# vdmotCtrl_v1.net
KiCad netlist of a schematic drawn in EAGLE
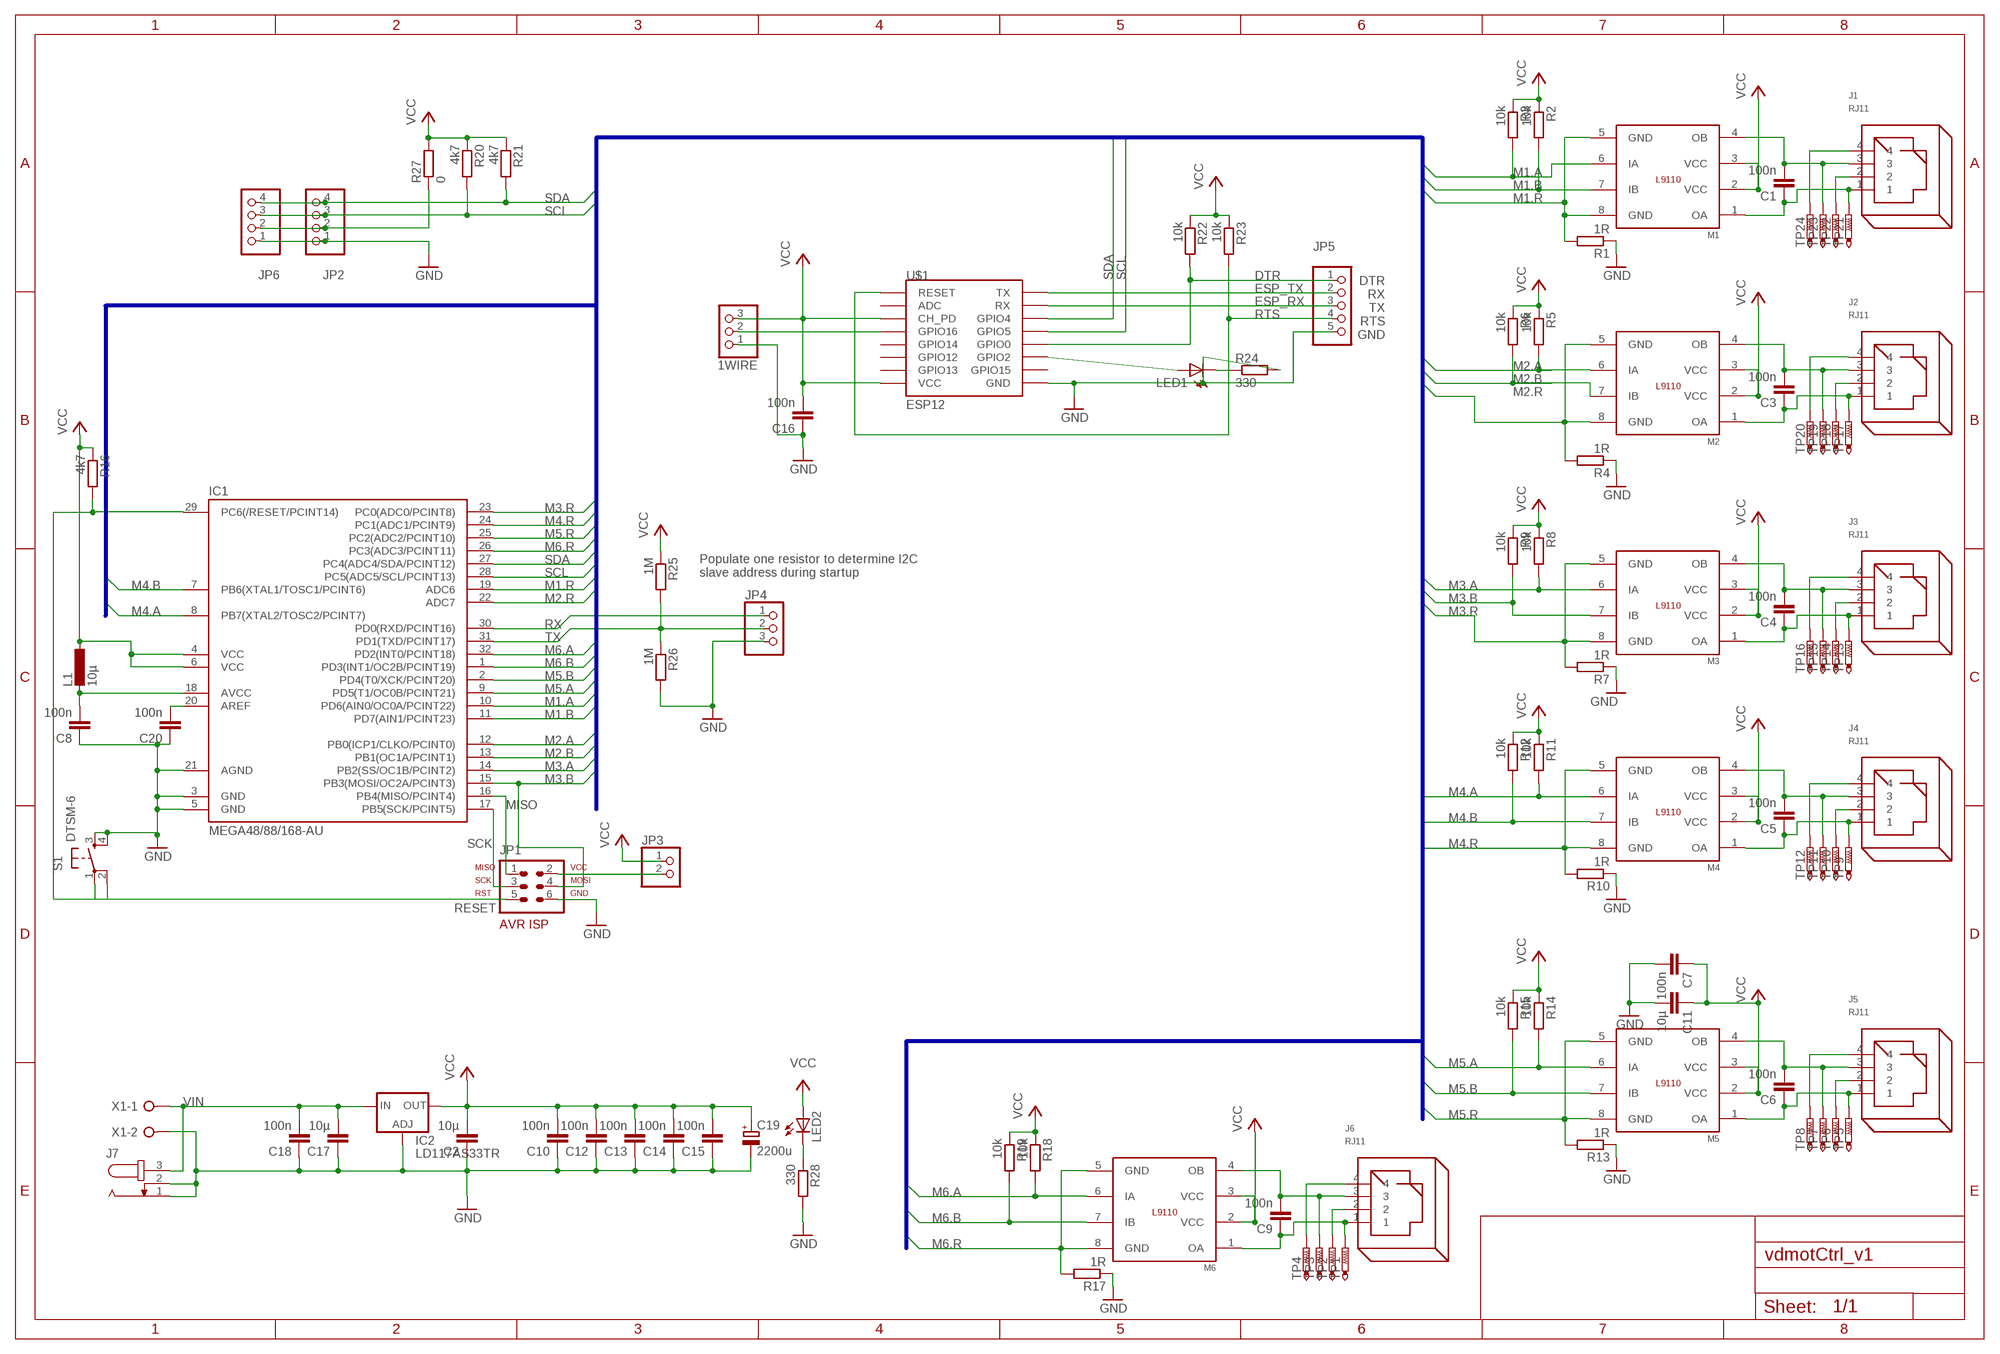
[diagram p0: schematic, sheet 1]

(export (version "E")
  (design (tool "Eeschema 10.0.6"))
  (components
    (comp (ref "1WIRE")
      (value "PINHD-1X3")
      (footprint "eagle-import:1X03")
      (libsource (lib "eagle-import") (part "PINHD-1X3"))
    )
    (comp (ref "C1")
      (value "100n")
      (footprint "eagle-import:C0805")
      (libsource (lib "eagle-import") (part "C-EUC0805"))
    )
    (comp (ref "C2")
      (value "10µ")
      (footprint "eagle-import:C0805")
      (libsource (lib "eagle-import") (part "C-EUC0805"))
    )
    (comp (ref "C3")
      (value "100n")
      (footprint "eagle-import:C0805")
      (libsource (lib "eagle-import") (part "C-EUC0805"))
    )
    (comp (ref "C4")
      (value "100n")
      (footprint "eagle-import:C0805")
      (libsource (lib "eagle-import") (part "C-EUC0805"))
    )
    (comp (ref "C5")
      (value "100n")
      (footprint "eagle-import:C0805")
      (libsource (lib "eagle-import") (part "C-EUC0805"))
    )
    (comp (ref "C6")
      (value "100n")
      (footprint "eagle-import:C0805")
      (libsource (lib "eagle-import") (part "C-EUC0805"))
    )
    (comp (ref "C7")
      (value "100n")
      (footprint "eagle-import:C0805")
      (libsource (lib "eagle-import") (part "C-EUC0805"))
    )
    (comp (ref "C8")
      (value "100n")
      (footprint "eagle-import:C0805")
      (libsource (lib "eagle-import") (part "C-EUC0805"))
    )
    (comp (ref "C9")
      (value "100n")
      (footprint "eagle-import:C0805")
      (libsource (lib "eagle-import") (part "C-EUC0805"))
    )
    (comp (ref "C10")
      (value "100n")
      (footprint "eagle-import:C0805")
      (libsource (lib "eagle-import") (part "C-EUC0805"))
    )
    (comp (ref "C11")
      (value "10µ")
      (footprint "eagle-import:C0805")
      (libsource (lib "eagle-import") (part "C-EUC0805"))
    )
    (comp (ref "C12")
      (value "100n")
      (footprint "eagle-import:C0805")
      (libsource (lib "eagle-import") (part "C-EUC0805"))
    )
    (comp (ref "C13")
      (value "100n")
      (footprint "eagle-import:C0805")
      (libsource (lib "eagle-import") (part "C-EUC0805"))
    )
    (comp (ref "C14")
      (value "100n")
      (footprint "eagle-import:C0805")
      (libsource (lib "eagle-import") (part "C-EUC0805"))
    )
    (comp (ref "C15")
      (value "100n")
      (footprint "eagle-import:C0805")
      (libsource (lib "eagle-import") (part "C-EUC0805"))
    )
    (comp (ref "C16")
      (value "100n")
      (footprint "eagle-import:C0805")
      (libsource (lib "eagle-import") (part "C-EUC0805"))
    )
    (comp (ref "C17")
      (value "10µ")
      (footprint "eagle-import:C0805")
      (libsource (lib "eagle-import") (part "C-EUC0805"))
    )
    (comp (ref "C18")
      (value "100n")
      (footprint "eagle-import:C0805")
      (libsource (lib "eagle-import") (part "C-EUC0805"))
    )
    (comp (ref "C19")
      (value "2200u")
      (footprint "eagle-import:E5-10,5")
      (libsource (lib "eagle-import") (part "CPOL-EUE5-10.5"))
    )
    (comp (ref "C20")
      (value "100n")
      (footprint "eagle-import:C0805")
      (libsource (lib "eagle-import") (part "C-EUC0805"))
    )
    (comp (ref "IC1")
      (value "MEGA48/88/168-AU")
      (footprint "eagle-import:TQFP32-08")
      (libsource (lib "eagle-import") (part "MEGA48/88/168-AU"))
    )
    (comp (ref "IC2")
      (value "LD117AS33TR")
      (footprint "eagle-import:SOT223")
      (libsource (lib "eagle-import") (part "LD117A?S33TR"))
    )
    (comp (ref "J1")
      (value "RJ11")
      (footprint "eagle-import:RJ11")
      (libsource (lib "eagle-import") (part "RJ11"))
    )
    (comp (ref "J2")
      (value "RJ11")
      (footprint "eagle-import:RJ11")
      (libsource (lib "eagle-import") (part "RJ11"))
    )
    (comp (ref "J3")
      (value "RJ11")
      (footprint "eagle-import:RJ11")
      (libsource (lib "eagle-import") (part "RJ11"))
    )
    (comp (ref "J4")
      (value "RJ11")
      (footprint "eagle-import:RJ11")
      (libsource (lib "eagle-import") (part "RJ11"))
    )
    (comp (ref "J5")
      (value "RJ11")
      (footprint "eagle-import:RJ11")
      (libsource (lib "eagle-import") (part "RJ11"))
    )
    (comp (ref "J6")
      (value "RJ11")
      (footprint "eagle-import:RJ11")
      (libsource (lib "eagle-import") (part "RJ11"))
    )
    (comp (ref "J7")
      (value "JACK-PLUG0")
      (footprint "eagle-import:SPC4077")
      (libsource (lib "eagle-import") (part "JACK-PLUG0"))
    )
    (comp (ref "JP1")
      (value "AVR-ISP-6VERT")
      (footprint "eagle-import:AVR-ISP-6")
      (libsource (lib "eagle-import") (part "AVR-ISP-6VERT"))
    )
    (comp (ref "JP2")
      (value "PINHD-1X4")
      (footprint "eagle-import:1X04")
      (libsource (lib "eagle-import") (part "PINHD-1X4"))
    )
    (comp (ref "JP3")
      (value "PINHD-1X2")
      (footprint "eagle-import:1X02")
      (libsource (lib "eagle-import") (part "PINHD-1X2"))
    )
    (comp (ref "JP4")
      (value "PINHD-1X3")
      (footprint "eagle-import:1X03")
      (libsource (lib "eagle-import") (part "PINHD-1X3"))
    )
    (comp (ref "JP5")
      (value "PINHD-1X5")
      (footprint "eagle-import:1X05")
      (libsource (lib "eagle-import") (part "PINHD-1X5"))
    )
    (comp (ref "JP6")
      (value "PINHD-1X4")
      (footprint "eagle-import:1X04")
      (libsource (lib "eagle-import") (part "PINHD-1X4"))
    )
    (comp (ref "L1")
      (value "10µ")
      (footprint "eagle-import:0204_7")
      (libsource (lib "eagle-import") (part "L-EU0204/7"))
    )
    (comp (ref "LED1")
      (value "RED")
      (footprint "eagle-import:SML0805")
      (libsource (lib "eagle-import") (part "LEDSML0805"))
    )
    (comp (ref "LED2")
      (value "RED")
      (footprint "eagle-import:SML0805")
      (libsource (lib "eagle-import") (part "LEDSML0805"))
    )
    (comp (ref "M1")
      (value "L9110")
      (footprint "eagle-import:SO8P")
      (libsource (lib "eagle-import") (part "L9110"))
    )
    (comp (ref "M2")
      (value "L9110")
      (footprint "eagle-import:SO8P")
      (libsource (lib "eagle-import") (part "L9110"))
    )
    (comp (ref "M3")
      (value "L9110")
      (footprint "eagle-import:SO8P")
      (libsource (lib "eagle-import") (part "L9110"))
    )
    (comp (ref "M4")
      (value "L9110")
      (footprint "eagle-import:SO8P")
      (libsource (lib "eagle-import") (part "L9110"))
    )
    (comp (ref "M5")
      (value "L9110")
      (footprint "eagle-import:SO8P")
      (libsource (lib "eagle-import") (part "L9110"))
    )
    (comp (ref "M6")
      (value "L9110")
      (footprint "eagle-import:SO8P")
      (libsource (lib "eagle-import") (part "L9110"))
    )
    (comp (ref "R1")
      (value "1R")
      (footprint "eagle-import:R0805")
      (libsource (lib "eagle-import") (part "R-EU_R0805"))
    )
    (comp (ref "R2")
      (value "10k")
      (footprint "eagle-import:R0805")
      (libsource (lib "eagle-import") (part "R-EU_R0805"))
    )
    (comp (ref "R3")
      (value "10k")
      (footprint "eagle-import:R0805")
      (libsource (lib "eagle-import") (part "R-EU_R0805"))
    )
    (comp (ref "R4")
      (value "1R")
      (footprint "eagle-import:R0805")
      (libsource (lib "eagle-import") (part "R-EU_R0805"))
    )
    (comp (ref "R5")
      (value "10k")
      (footprint "eagle-import:R0805")
      (libsource (lib "eagle-import") (part "R-EU_R0805"))
    )
    (comp (ref "R6")
      (value "10k")
      (footprint "eagle-import:R0805")
      (libsource (lib "eagle-import") (part "R-EU_R0805"))
    )
    (comp (ref "R7")
      (value "1R")
      (footprint "eagle-import:R0805")
      (libsource (lib "eagle-import") (part "R-EU_R0805"))
    )
    (comp (ref "R8")
      (value "10k")
      (footprint "eagle-import:R0805")
      (libsource (lib "eagle-import") (part "R-EU_R0805"))
    )
    (comp (ref "R9")
      (value "10k")
      (footprint "eagle-import:R0805")
      (libsource (lib "eagle-import") (part "R-EU_R0805"))
    )
    (comp (ref "R10")
      (value "1R")
      (footprint "eagle-import:R0805")
      (libsource (lib "eagle-import") (part "R-EU_R0805"))
    )
    (comp (ref "R11")
      (value "10k")
      (footprint "eagle-import:R0805")
      (libsource (lib "eagle-import") (part "R-EU_R0805"))
    )
    (comp (ref "R12")
      (value "10k")
      (footprint "eagle-import:R0805")
      (libsource (lib "eagle-import") (part "R-EU_R0805"))
    )
    (comp (ref "R13")
      (value "1R")
      (footprint "eagle-import:R0805")
      (libsource (lib "eagle-import") (part "R-EU_R0805"))
    )
    (comp (ref "R14")
      (value "10k")
      (footprint "eagle-import:R0805")
      (libsource (lib "eagle-import") (part "R-EU_R0805"))
    )
    (comp (ref "R15")
      (value "10k")
      (footprint "eagle-import:R0805")
      (libsource (lib "eagle-import") (part "R-EU_R0805"))
    )
    (comp (ref "R16")
      (value "4k7")
      (footprint "eagle-import:R0805")
      (libsource (lib "eagle-import") (part "R-EU_R0805"))
    )
    (comp (ref "R17")
      (value "1R")
      (footprint "eagle-import:R0805")
      (libsource (lib "eagle-import") (part "R-EU_R0805"))
    )
    (comp (ref "R18")
      (value "10k")
      (footprint "eagle-import:R0805")
      (libsource (lib "eagle-import") (part "R-EU_R0805"))
    )
    (comp (ref "R19")
      (value "10k")
      (footprint "eagle-import:R0805")
      (libsource (lib "eagle-import") (part "R-EU_R0805"))
    )
    (comp (ref "R20")
      (value "4k7")
      (footprint "eagle-import:R0805")
      (libsource (lib "eagle-import") (part "R-EU_R0805"))
    )
    (comp (ref "R21")
      (value "4k7")
      (footprint "eagle-import:R0805")
      (libsource (lib "eagle-import") (part "R-EU_R0805"))
    )
    (comp (ref "R22")
      (value "10k")
      (footprint "eagle-import:R0805")
      (libsource (lib "eagle-import") (part "R-EU_R0805"))
    )
    (comp (ref "R23")
      (value "10k")
      (footprint "eagle-import:R0805")
      (libsource (lib "eagle-import") (part "R-EU_R0805"))
    )
    (comp (ref "R24")
      (value "330")
      (footprint "eagle-import:R0805")
      (libsource (lib "eagle-import") (part "R-EU_R0805"))
    )
    (comp (ref "R25")
      (value "1M")
      (footprint "eagle-import:R0805")
      (libsource (lib "eagle-import") (part "R-EU_R0805"))
    )
    (comp (ref "R26")
      (value "1M")
      (footprint "eagle-import:R0805")
      (libsource (lib "eagle-import") (part "R-EU_R0805"))
    )
    (comp (ref "R27")
      (value "0")
      (footprint "eagle-import:M0805")
      (libsource (lib "eagle-import") (part "R-EU_M0805"))
    )
    (comp (ref "R28")
      (value "330")
      (footprint "eagle-import:R0805")
      (libsource (lib "eagle-import") (part "R-EU_R0805"))
    )
    (comp (ref "S1")
      (value "DTSM-6")
      (footprint "eagle-import:DTSM-6")
      (libsource (lib "eagle-import") (part "DTSM-6"))
    )
    (comp (ref "TP1")
      (value "PTR1TP15SQ")
      (footprint "eagle-import:TP15SQ")
      (libsource (lib "eagle-import") (part "PTR1TP15SQ"))
    )
    (comp (ref "TP2")
      (value "PTR1TP15SQ")
      (footprint "eagle-import:TP15SQ")
      (libsource (lib "eagle-import") (part "PTR1TP15SQ"))
    )
    (comp (ref "TP3")
      (value "PTR1TP15SQ")
      (footprint "eagle-import:TP15SQ")
      (libsource (lib "eagle-import") (part "PTR1TP15SQ"))
    )
    (comp (ref "TP4")
      (value "PTR1TP15SQ")
      (footprint "eagle-import:TP15SQ")
      (libsource (lib "eagle-import") (part "PTR1TP15SQ"))
    )
    (comp (ref "TP5")
      (value "PTR1TP15SQ")
      (footprint "eagle-import:TP15SQ")
      (libsource (lib "eagle-import") (part "PTR1TP15SQ"))
    )
    (comp (ref "TP6")
      (value "PTR1TP15SQ")
      (footprint "eagle-import:TP15SQ")
      (libsource (lib "eagle-import") (part "PTR1TP15SQ"))
    )
    (comp (ref "TP7")
      (value "PTR1TP15SQ")
      (footprint "eagle-import:TP15SQ")
      (libsource (lib "eagle-import") (part "PTR1TP15SQ"))
    )
    (comp (ref "TP8")
      (value "PTR1TP15SQ")
      (footprint "eagle-import:TP15SQ")
      (libsource (lib "eagle-import") (part "PTR1TP15SQ"))
    )
    (comp (ref "TP9")
      (value "PTR1TP15SQ")
      (footprint "eagle-import:TP15SQ")
      (libsource (lib "eagle-import") (part "PTR1TP15SQ"))
    )
    (comp (ref "TP10")
      (value "PTR1TP15SQ")
      (footprint "eagle-import:TP15SQ")
      (libsource (lib "eagle-import") (part "PTR1TP15SQ"))
    )
    (comp (ref "TP11")
      (value "PTR1TP15SQ")
      (footprint "eagle-import:TP15SQ")
      (libsource (lib "eagle-import") (part "PTR1TP15SQ"))
    )
    (comp (ref "TP12")
      (value "PTR1TP15SQ")
      (footprint "eagle-import:TP15SQ")
      (libsource (lib "eagle-import") (part "PTR1TP15SQ"))
    )
    (comp (ref "TP13")
      (value "PTR1TP15SQ")
      (footprint "eagle-import:TP15SQ")
      (libsource (lib "eagle-import") (part "PTR1TP15SQ"))
    )
    (comp (ref "TP14")
      (value "PTR1TP15SQ")
      (footprint "eagle-import:TP15SQ")
      (libsource (lib "eagle-import") (part "PTR1TP15SQ"))
    )
    (comp (ref "TP15")
      (value "PTR1TP15SQ")
      (footprint "eagle-import:TP15SQ")
      (libsource (lib "eagle-import") (part "PTR1TP15SQ"))
    )
    (comp (ref "TP16")
      (value "PTR1TP15SQ")
      (footprint "eagle-import:TP15SQ")
      (libsource (lib "eagle-import") (part "PTR1TP15SQ"))
    )
    (comp (ref "TP17")
      (value "PTR1TP15SQ")
      (footprint "eagle-import:TP15SQ")
      (libsource (lib "eagle-import") (part "PTR1TP15SQ"))
    )
    (comp (ref "TP18")
      (value "PTR1TP15SQ")
      (footprint "eagle-import:TP15SQ")
      (libsource (lib "eagle-import") (part "PTR1TP15SQ"))
    )
    (comp (ref "TP19")
      (value "PTR1TP15SQ")
      (footprint "eagle-import:TP15SQ")
      (libsource (lib "eagle-import") (part "PTR1TP15SQ"))
    )
    (comp (ref "TP20")
      (value "PTR1TP15SQ")
      (footprint "eagle-import:TP15SQ")
      (libsource (lib "eagle-import") (part "PTR1TP15SQ"))
    )
    (comp (ref "TP21")
      (value "PTR1TP15SQ")
      (footprint "eagle-import:TP15SQ")
      (libsource (lib "eagle-import") (part "PTR1TP15SQ"))
    )
    (comp (ref "TP22")
      (value "PTR1TP15SQ")
      (footprint "eagle-import:TP15SQ")
      (libsource (lib "eagle-import") (part "PTR1TP15SQ"))
    )
    (comp (ref "TP23")
      (value "PTR1TP15SQ")
      (footprint "eagle-import:TP15SQ")
      (libsource (lib "eagle-import") (part "PTR1TP15SQ"))
    )
    (comp (ref "TP24")
      (value "PTR1TP15SQ")
      (footprint "eagle-import:TP15SQ")
      (libsource (lib "eagle-import") (part "PTR1TP15SQ"))
    )
    (comp (ref "U$1")
      (value "ESP12")
      (footprint "eagle-import:ESP12")
      (libsource (lib "eagle-import") (part "ESP12"))
    )
    (comp (ref "X1")
      (value "W237-02P")
      (footprint "eagle-import:W237-132")
      (libsource (lib "eagle-import") (part "W237-02P"))
    )
  )
  (nets
    (net (code "1") (name "/DTR") (class "Default")
      (node (ref "JP5") (pin "1") (pinfunction "1_1") (pintype "passive"))
      (node (ref "R22") (pin "2") (pinfunction "2_2") (pintype "passive"))
      (node (ref "U$1") (pin "GPIO0") (pinfunction "GPIO0_GPIO0") (pintype "bidirectional"))
    )
    (net (code "2") (name "/ESP_RX") (class "Default")
      (node (ref "JP5") (pin "3") (pinfunction "3_3") (pintype "passive"))
      (node (ref "U$1") (pin "RX") (pinfunction "RX_RX") (pintype "bidirectional"))
    )
    (net (code "3") (name "/ESP_TX") (class "Default")
      (node (ref "JP5") (pin "2") (pinfunction "2_2") (pintype "passive"))
      (node (ref "U$1") (pin "TX") (pinfunction "TX_TX") (pintype "bidirectional"))
    )
    (net (code "4") (name "/M1.A") (class "Default")
      (node (ref "IC1") (pin "10") (pinfunction "PD6(AIN0/OC0A/PCINT22)_10") (pintype "bidirectional"))
      (node (ref "M1") (pin "6") (pinfunction "IA_6") (pintype "bidirectional"))
      (node (ref "R3") (pin "2") (pinfunction "2_2") (pintype "passive"))
    )
    (net (code "5") (name "/M1.B") (class "Default")
      (node (ref "IC1") (pin "11") (pinfunction "PD7(AIN1/PCINT23)_11") (pintype "bidirectional"))
      (node (ref "M1") (pin "7") (pinfunction "IB_7") (pintype "bidirectional"))
      (node (ref "R2") (pin "2") (pinfunction "2_2") (pintype "passive"))
    )
    (net (code "6") (name "/M1.R") (class "Default")
      (node (ref "IC1") (pin "19") (pinfunction "ADC6_19") (pintype "passive"))
      (node (ref "M1") (pin "5") (pinfunction "GND_5") (pintype "bidirectional"))
      (node (ref "M1") (pin "8") (pinfunction "GND_8") (pintype "bidirectional"))
      (node (ref "R1") (pin "2") (pinfunction "2_2") (pintype "passive"))
    )
    (net (code "7") (name "/M2.A") (class "Default")
      (node (ref "IC1") (pin "12") (pinfunction "PB0(ICP1/CLKO/PCINT0)_12") (pintype "bidirectional"))
      (node (ref "M2") (pin "6") (pinfunction "IA_6") (pintype "bidirectional"))
      (node (ref "R5") (pin "2") (pinfunction "2_2") (pintype "passive"))
    )
    (net (code "8") (name "/M2.B") (class "Default")
      (node (ref "IC1") (pin "13") (pinfunction "PB1(OC1A/PCINT1)_13") (pintype "bidirectional"))
      (node (ref "M2") (pin "7") (pinfunction "IB_7") (pintype "bidirectional"))
      (node (ref "R6") (pin "2") (pinfunction "2_2") (pintype "passive"))
    )
    (net (code "9") (name "/M2.R") (class "Default")
      (node (ref "IC1") (pin "22") (pinfunction "ADC7_22") (pintype "passive"))
      (node (ref "M2") (pin "5") (pinfunction "GND_5") (pintype "bidirectional"))
      (node (ref "M2") (pin "8") (pinfunction "GND_8") (pintype "bidirectional"))
      (node (ref "R4") (pin "2") (pinfunction "2_2") (pintype "passive"))
    )
    (net (code "10") (name "/M3.A") (class "Default")
      (node (ref "IC1") (pin "14") (pinfunction "PB2(SS/OC1B/PCINT2)_14") (pintype "bidirectional"))
      (node (ref "M3") (pin "6") (pinfunction "IA_6") (pintype "bidirectional"))
      (node (ref "R8") (pin "2") (pinfunction "2_2") (pintype "passive"))
    )
    (net (code "11") (name "/M3.B") (class "Default")
      (node (ref "IC1") (pin "15") (pinfunction "PB3(MOSI/OC2A/PCINT3)_15") (pintype "bidirectional"))
      (node (ref "JP1") (pin "4") (pinfunction "4_4") (pintype "passive"))
      (node (ref "M3") (pin "7") (pinfunction "IB_7") (pintype "bidirectional"))
      (node (ref "R9") (pin "2") (pinfunction "2_2") (pintype "passive"))
    )
    (net (code "12") (name "/M3.R") (class "Default")
      (node (ref "IC1") (pin "23") (pinfunction "PC0(ADC0/PCINT8)_23") (pintype "bidirectional"))
      (node (ref "M3") (pin "5") (pinfunction "GND_5") (pintype "bidirectional"))
      (node (ref "M3") (pin "8") (pinfunction "GND_8") (pintype "bidirectional"))
      (node (ref "R7") (pin "2") (pinfunction "2_2") (pintype "passive"))
    )
    (net (code "13") (name "/M4.A") (class "Default")
      (node (ref "IC1") (pin "8") (pinfunction "PB7(XTAL2/TOSC2/PCINT7)_8") (pintype "bidirectional"))
      (node (ref "M4") (pin "6") (pinfunction "IA_6") (pintype "bidirectional"))
      (node (ref "R11") (pin "2") (pinfunction "2_2") (pintype "passive"))
    )
    (net (code "14") (name "/M4.B") (class "Default")
      (node (ref "IC1") (pin "7") (pinfunction "PB6(XTAL1/TOSC1/PCINT6)_7") (pintype "bidirectional"))
      (node (ref "M4") (pin "7") (pinfunction "IB_7") (pintype "bidirectional"))
      (node (ref "R12") (pin "2") (pinfunction "2_2") (pintype "passive"))
    )
    (net (code "15") (name "/M4.R") (class "Default")
      (node (ref "IC1") (pin "24") (pinfunction "PC1(ADC1/PCINT9)_24") (pintype "bidirectional"))
      (node (ref "M4") (pin "5") (pinfunction "GND_5") (pintype "bidirectional"))
      (node (ref "M4") (pin "8") (pinfunction "GND_8") (pintype "bidirectional"))
      (node (ref "R10") (pin "2") (pinfunction "2_2") (pintype "passive"))
    )
    (net (code "16") (name "/M5.A") (class "Default")
      (node (ref "IC1") (pin "9") (pinfunction "PD5(T1/OC0B/PCINT21)_9") (pintype "bidirectional"))
      (node (ref "M5") (pin "6") (pinfunction "IA_6") (pintype "bidirectional"))
      (node (ref "R14") (pin "2") (pinfunction "2_2") (pintype "passive"))
    )
    (net (code "17") (name "/M5.B") (class "Default")
      (node (ref "IC1") (pin "2") (pinfunction "PD4(T0/XCK/PCINT20)_2") (pintype "bidirectional"))
      (node (ref "M5") (pin "7") (pinfunction "IB_7") (pintype "bidirectional"))
      (node (ref "R15") (pin "2") (pinfunction "2_2") (pintype "passive"))
    )
    (net (code "18") (name "/M5.R") (class "Default")
      (node (ref "IC1") (pin "25") (pinfunction "PC2(ADC2/PCINT10)_25") (pintype "bidirectional"))
      (node (ref "M5") (pin "5") (pinfunction "GND_5") (pintype "bidirectional"))
      (node (ref "M5") (pin "8") (pinfunction "GND_8") (pintype "bidirectional"))
      (node (ref "R13") (pin "2") (pinfunction "2_2") (pintype "passive"))
    )
    (net (code "19") (name "/M6.A") (class "Default")
      (node (ref "IC1") (pin "32") (pinfunction "PD2(INT0/PCINT18)_32") (pintype "bidirectional"))
      (node (ref "M6") (pin "6") (pinfunction "IA_6") (pintype "bidirectional"))
      (node (ref "R18") (pin "2") (pinfunction "2_2") (pintype "passive"))
    )
    (net (code "20") (name "/M6.B") (class "Default")
      (node (ref "IC1") (pin "1") (pinfunction "PD3(INT1/OC2B/PCINT19)_1") (pintype "bidirectional"))
      (node (ref "M6") (pin "7") (pinfunction "IB_7") (pintype "bidirectional"))
      (node (ref "R19") (pin "2") (pinfunction "2_2") (pintype "passive"))
    )
    (net (code "21") (name "/M6.R") (class "Default")
      (node (ref "IC1") (pin "26") (pinfunction "PC3(ADC3/PCINT11)_26") (pintype "bidirectional"))
      (node (ref "M6") (pin "5") (pinfunction "GND_5") (pintype "bidirectional"))
      (node (ref "M6") (pin "8") (pinfunction "GND_8") (pintype "bidirectional"))
      (node (ref "R17") (pin "2") (pinfunction "2_2") (pintype "passive"))
    )
    (net (code "22") (name "/MISO") (class "Default")
      (node (ref "IC1") (pin "16") (pinfunction "PB4(MISO/PCINT4)_16") (pintype "bidirectional"))
      (node (ref "JP1") (pin "1") (pinfunction "1_1") (pintype "passive"))
    )
    (net (code "23") (name "/RESET") (class "Default")
      (node (ref "IC1") (pin "29") (pinfunction "PC6(/RESET/PCINT14)_29") (pintype "bidirectional"))
      (node (ref "JP1") (pin "5") (pinfunction "5_5") (pintype "passive"))
      (node (ref "R16") (pin "2") (pinfunction "2_2") (pintype "passive"))
      (node (ref "S1") (pin "1") (pinfunction "1_1") (pintype "passive"))
      (node (ref "S1") (pin "2") (pinfunction "2_2") (pintype "passive"))
    )
    (net (code "24") (name "/RTS") (class "Default")
      (node (ref "JP5") (pin "4") (pinfunction "4_4") (pintype "passive"))
      (node (ref "R23") (pin "2") (pinfunction "2_2") (pintype "passive"))
      (node (ref "U$1") (pin "RESET") (pinfunction "RESET_RESET") (pintype "bidirectional"))
    )
    (net (code "25") (name "/RX") (class "Default")
      (node (ref "IC1") (pin "30") (pinfunction "PD0(RXD/PCINT16)_30") (pintype "bidirectional"))
      (node (ref "JP4") (pin "1") (pinfunction "1_1") (pintype "passive"))
    )
    (net (code "26") (name "/SCK") (class "Default")
      (node (ref "IC1") (pin "17") (pinfunction "PB5(SCK/PCINT5)_17") (pintype "bidirectional"))
      (node (ref "JP1") (pin "3") (pinfunction "3_3") (pintype "passive"))
    )
    (net (code "27") (name "/SCL") (class "Default")
      (node (ref "IC1") (pin "28") (pinfunction "PC5(ADC5/SCL/PCINT13)_28") (pintype "bidirectional"))
      (node (ref "JP2") (pin "3") (pinfunction "3_3") (pintype "passive"))
      (node (ref "JP6") (pin "3") (pinfunction "3_3") (pintype "passive"))
      (node (ref "R20") (pin "2") (pinfunction "2_2") (pintype "passive"))
      (node (ref "U$1") (pin "GPIO5") (pinfunction "GPIO5_GPIO5") (pintype "bidirectional"))
    )
    (net (code "28") (name "/SDA") (class "Default")
      (node (ref "IC1") (pin "27") (pinfunction "PC4(ADC4/SDA/PCINT12)_27") (pintype "bidirectional"))
      (node (ref "JP2") (pin "4") (pinfunction "4_4") (pintype "passive"))
      (node (ref "JP6") (pin "4") (pinfunction "4_4") (pintype "passive"))
      (node (ref "R21") (pin "2") (pinfunction "2_2") (pintype "passive"))
      (node (ref "U$1") (pin "GPIO4") (pinfunction "GPIO4_GPIO4") (pintype "bidirectional"))
    )
    (net (code "29") (name "/TX") (class "Default")
      (node (ref "IC1") (pin "31") (pinfunction "PD1(TXD/PCINT17)_31") (pintype "bidirectional"))
      (node (ref "JP4") (pin "2") (pinfunction "2_2") (pintype "passive"))
      (node (ref "R25") (pin "2") (pinfunction "2_2") (pintype "passive"))
      (node (ref "R26") (pin "1") (pinfunction "1_1") (pintype "passive"))
    )
    (net (code "30") (name "/VIN") (class "Default")
      (node (ref "C17") (pin "2") (pinfunction "2_2") (pintype "passive"))
      (node (ref "C18") (pin "2") (pinfunction "2_2") (pintype "passive"))
      (node (ref "IC2") (pin "3") (pinfunction "IN_3") (pintype "input"))
      (node (ref "J7") (pin "3") (pinfunction "3_3") (pintype "passive"))
      (node (ref "X1") (pin "1") (pinfunction "KL_1") (pintype "passive"))
    )
    (net (code "31") (name "GND") (class "Default")
      (node (ref "1WIRE") (pin "1") (pinfunction "1_1") (pintype "passive"))
      (node (ref "C10") (pin "1") (pinfunction "1_1") (pintype "passive"))
      (node (ref "C11") (pin "2") (pinfunction "2_2") (pintype "passive"))
      (node (ref "C12") (pin "1") (pinfunction "1_1") (pintype "passive"))
      (node (ref "C13") (pin "1") (pinfunction "1_1") (pintype "passive"))
      (node (ref "C14") (pin "1") (pinfunction "1_1") (pintype "passive"))
      (node (ref "C15") (pin "1") (pinfunction "1_1") (pintype "passive"))
      (node (ref "C16") (pin "1") (pinfunction "1_1") (pintype "passive"))
      (node (ref "C17") (pin "1") (pinfunction "1_1") (pintype "passive"))
      (node (ref "C18") (pin "1") (pinfunction "1_1") (pintype "passive"))
      (node (ref "C19") (pin "-") (pinfunction "-_-") (pintype "passive"))
      (node (ref "C2") (pin "1") (pinfunction "1_1") (pintype "passive"))
      (node (ref "C20") (pin "1") (pinfunction "1_1") (pintype "passive"))
      (node (ref "C7") (pin "2") (pinfunction "2_2") (pintype "passive"))
      (node (ref "C8") (pin "1") (pinfunction "1_1") (pintype "passive"))
      (node (ref "IC1") (pin "21") (pinfunction "AGND_21") (pintype "power_in"))
      (node (ref "IC1") (pin "3") (pinfunction "GND_3") (pintype "power_in"))
      (node (ref "IC1") (pin "5") (pinfunction "GND_5") (pintype "power_in"))
      (node (ref "IC2") (pin "1") (pinfunction "ADJ_1") (pintype "input"))
      (node (ref "J7") (pin "1") (pinfunction "1_1") (pintype "passive"))
      (node (ref "J7") (pin "2") (pinfunction "2_2") (pintype "passive"))
      (node (ref "JP1") (pin "6") (pinfunction "6_6") (pintype "passive"))
      (node (ref "JP2") (pin "1") (pinfunction "1_1") (pintype "passive"))
      (node (ref "JP4") (pin "3") (pinfunction "3_3") (pintype "passive"))
      (node (ref "JP5") (pin "5") (pinfunction "5_5") (pintype "passive"))
      (node (ref "JP6") (pin "1") (pinfunction "1_1") (pintype "passive"))
      (node (ref "R1") (pin "1") (pinfunction "1_1") (pintype "passive"))
      (node (ref "R10") (pin "1") (pinfunction "1_1") (pintype "passive"))
      (node (ref "R13") (pin "1") (pinfunction "1_1") (pintype "passive"))
      (node (ref "R17") (pin "1") (pinfunction "1_1") (pintype "passive"))
      (node (ref "R24") (pin "2") (pinfunction "2_2") (pintype "passive"))
      (node (ref "R26") (pin "2") (pinfunction "2_2") (pintype "passive"))
      (node (ref "R28") (pin "2") (pinfunction "2_2") (pintype "passive"))
      (node (ref "R4") (pin "1") (pinfunction "1_1") (pintype "passive"))
      (node (ref "R7") (pin "1") (pinfunction "1_1") (pintype "passive"))
      (node (ref "S1") (pin "3") (pinfunction "3_3") (pintype "passive"))
      (node (ref "S1") (pin "4") (pinfunction "4_4") (pintype "passive"))
      (node (ref "U$1") (pin "GND") (pinfunction "GND_GND") (pintype "bidirectional"))
      (node (ref "X1") (pin "2") (pinfunction "KL_2") (pintype "passive"))
    )
    (net (code "32") (name "Net-(1WIRE-Pad2)") (class "Default")
      (node (ref "1WIRE") (pin "2") (pinfunction "2_2") (pintype "passive"))
      (node (ref "U$1") (pin "GPIO16") (pinfunction "GPIO16_GPIO16") (pintype "bidirectional"))
    )
    (net (code "33") (name "Net-(IC1-AREF)") (class "Default")
      (node (ref "C20") (pin "2") (pinfunction "2_2") (pintype "passive"))
      (node (ref "IC1") (pin "20") (pinfunction "AREF_20") (pintype "passive"))
    )
    (net (code "34") (name "Net-(IC1-AVCC)") (class "Default")
      (node (ref "C8") (pin "2") (pinfunction "2_2") (pintype "passive"))
      (node (ref "IC1") (pin "18") (pinfunction "AVCC_18") (pintype "passive"))
      (node (ref "L1") (pin "2") (pinfunction "2_2") (pintype "passive"))
    )
    (net (code "35") (name "Net-(J1-Pad2)") (class "Default")
      (node (ref "J1") (pin "2") (pinfunction "2_2") (pintype "bidirectional"))
      (node (ref "TP22") (pin "TP") (pinfunction "TP_TP") (pintype "input"))
    )
    (net (code "36") (name "Net-(J1-Pad4)") (class "Default")
      (node (ref "J1") (pin "4") (pinfunction "4_4") (pintype "bidirectional"))
      (node (ref "TP24") (pin "TP") (pinfunction "TP_TP") (pintype "input"))
    )
    (net (code "37") (name "Net-(J2-Pad2)") (class "Default")
      (node (ref "J2") (pin "2") (pinfunction "2_2") (pintype "bidirectional"))
      (node (ref "TP18") (pin "TP") (pinfunction "TP_TP") (pintype "input"))
    )
    (net (code "38") (name "Net-(J2-Pad4)") (class "Default")
      (node (ref "J2") (pin "4") (pinfunction "4_4") (pintype "bidirectional"))
      (node (ref "TP20") (pin "TP") (pinfunction "TP_TP") (pintype "input"))
    )
    (net (code "39") (name "Net-(J3-Pad2)") (class "Default")
      (node (ref "J3") (pin "2") (pinfunction "2_2") (pintype "bidirectional"))
      (node (ref "TP14") (pin "TP") (pinfunction "TP_TP") (pintype "input"))
    )
    (net (code "40") (name "Net-(J3-Pad4)") (class "Default")
      (node (ref "J3") (pin "4") (pinfunction "4_4") (pintype "bidirectional"))
      (node (ref "TP16") (pin "TP") (pinfunction "TP_TP") (pintype "input"))
    )
    (net (code "41") (name "Net-(J4-Pad2)") (class "Default")
      (node (ref "J4") (pin "2") (pinfunction "2_2") (pintype "bidirectional"))
      (node (ref "TP10") (pin "TP") (pinfunction "TP_TP") (pintype "input"))
    )
    (net (code "42") (name "Net-(J4-Pad4)") (class "Default")
      (node (ref "J4") (pin "4") (pinfunction "4_4") (pintype "bidirectional"))
      (node (ref "TP12") (pin "TP") (pinfunction "TP_TP") (pintype "input"))
    )
    (net (code "43") (name "Net-(J5-Pad2)") (class "Default")
      (node (ref "J5") (pin "2") (pinfunction "2_2") (pintype "bidirectional"))
      (node (ref "TP6") (pin "TP") (pinfunction "TP_TP") (pintype "input"))
    )
    (net (code "44") (name "Net-(J5-Pad4)") (class "Default")
      (node (ref "J5") (pin "4") (pinfunction "4_4") (pintype "bidirectional"))
      (node (ref "TP8") (pin "TP") (pinfunction "TP_TP") (pintype "input"))
    )
    (net (code "45") (name "Net-(J6-Pad2)") (class "Default")
      (node (ref "J6") (pin "2") (pinfunction "2_2") (pintype "bidirectional"))
      (node (ref "TP2") (pin "TP") (pinfunction "TP_TP") (pintype "input"))
    )
    (net (code "46") (name "Net-(J6-Pad4)") (class "Default")
      (node (ref "J6") (pin "4") (pinfunction "4_4") (pintype "bidirectional"))
      (node (ref "TP4") (pin "TP") (pinfunction "TP_TP") (pintype "input"))
    )
    (net (code "47") (name "Net-(JP1-Pad2)") (class "Default")
      (node (ref "JP1") (pin "2") (pinfunction "2_2") (pintype "passive"))
      (node (ref "JP3") (pin "2") (pinfunction "2_2") (pintype "passive"))
    )
    (net (code "48") (name "Net-(JP2-Pad2)") (class "Default")
      (node (ref "JP2") (pin "2") (pinfunction "2_2") (pintype "passive"))
      (node (ref "JP6") (pin "2") (pinfunction "2_2") (pintype "passive"))
      (node (ref "R27") (pin "1") (pinfunction "1_1") (pintype "passive"))
    )
    (net (code "49") (name "Net-(LED1-PadA)") (class "Default")
      (node (ref "LED1") (pin "A") (pinfunction "A_A") (pintype "passive"))
      (node (ref "U$1") (pin "GPIO2") (pinfunction "GPIO2_GPIO2") (pintype "bidirectional"))
    )
    (net (code "50") (name "Net-(LED1-PadC)") (class "Default")
      (node (ref "LED1") (pin "C") (pinfunction "C_C") (pintype "passive"))
      (node (ref "R24") (pin "1") (pinfunction "1_1") (pintype "passive"))
    )
    (net (code "51") (name "Net-(LED2-PadC)") (class "Default")
      (node (ref "LED2") (pin "C") (pinfunction "C_C") (pintype "passive"))
      (node (ref "R28") (pin "1") (pinfunction "1_1") (pintype "passive"))
    )
    (net (code "52") (name "Net-(M1-OA)") (class "Default")
      (node (ref "C1") (pin "1") (pinfunction "1_1") (pintype "passive"))
      (node (ref "J1") (pin "1") (pinfunction "1_1") (pintype "bidirectional"))
      (node (ref "M1") (pin "1") (pinfunction "OA_1") (pintype "bidirectional"))
      (node (ref "TP21") (pin "TP") (pinfunction "TP_TP") (pintype "input"))
    )
    (net (code "53") (name "Net-(M1-OB)") (class "Default")
      (node (ref "C1") (pin "2") (pinfunction "2_2") (pintype "passive"))
      (node (ref "J1") (pin "3") (pinfunction "3_3") (pintype "bidirectional"))
      (node (ref "M1") (pin "4") (pinfunction "OB_4") (pintype "bidirectional"))
      (node (ref "TP23") (pin "TP") (pinfunction "TP_TP") (pintype "input"))
    )
    (net (code "54") (name "Net-(M2-OA)") (class "Default")
      (node (ref "C3") (pin "1") (pinfunction "1_1") (pintype "passive"))
      (node (ref "J2") (pin "1") (pinfunction "1_1") (pintype "bidirectional"))
      (node (ref "M2") (pin "1") (pinfunction "OA_1") (pintype "bidirectional"))
      (node (ref "TP17") (pin "TP") (pinfunction "TP_TP") (pintype "input"))
    )
    (net (code "55") (name "Net-(M2-OB)") (class "Default")
      (node (ref "C3") (pin "2") (pinfunction "2_2") (pintype "passive"))
      (node (ref "J2") (pin "3") (pinfunction "3_3") (pintype "bidirectional"))
      (node (ref "M2") (pin "4") (pinfunction "OB_4") (pintype "bidirectional"))
      (node (ref "TP19") (pin "TP") (pinfunction "TP_TP") (pintype "input"))
    )
    (net (code "56") (name "Net-(M3-OA)") (class "Default")
      (node (ref "C4") (pin "1") (pinfunction "1_1") (pintype "passive"))
      (node (ref "J3") (pin "1") (pinfunction "1_1") (pintype "bidirectional"))
      (node (ref "M3") (pin "1") (pinfunction "OA_1") (pintype "bidirectional"))
      (node (ref "TP13") (pin "TP") (pinfunction "TP_TP") (pintype "input"))
    )
    (net (code "57") (name "Net-(M3-OB)") (class "Default")
      (node (ref "C4") (pin "2") (pinfunction "2_2") (pintype "passive"))
      (node (ref "J3") (pin "3") (pinfunction "3_3") (pintype "bidirectional"))
      (node (ref "M3") (pin "4") (pinfunction "OB_4") (pintype "bidirectional"))
      (node (ref "TP15") (pin "TP") (pinfunction "TP_TP") (pintype "input"))
    )
    (net (code "58") (name "Net-(M4-OA)") (class "Default")
      (node (ref "C5") (pin "1") (pinfunction "1_1") (pintype "passive"))
      (node (ref "J4") (pin "1") (pinfunction "1_1") (pintype "bidirectional"))
      (node (ref "M4") (pin "1") (pinfunction "OA_1") (pintype "bidirectional"))
      (node (ref "TP9") (pin "TP") (pinfunction "TP_TP") (pintype "input"))
    )
    (net (code "59") (name "Net-(M4-OB)") (class "Default")
      (node (ref "C5") (pin "2") (pinfunction "2_2") (pintype "passive"))
      (node (ref "J4") (pin "3") (pinfunction "3_3") (pintype "bidirectional"))
      (node (ref "M4") (pin "4") (pinfunction "OB_4") (pintype "bidirectional"))
      (node (ref "TP11") (pin "TP") (pinfunction "TP_TP") (pintype "input"))
    )
    (net (code "60") (name "Net-(M5-OA)") (class "Default")
      (node (ref "C6") (pin "1") (pinfunction "1_1") (pintype "passive"))
      (node (ref "J5") (pin "1") (pinfunction "1_1") (pintype "bidirectional"))
      (node (ref "M5") (pin "1") (pinfunction "OA_1") (pintype "bidirectional"))
      (node (ref "TP5") (pin "TP") (pinfunction "TP_TP") (pintype "input"))
    )
    (net (code "61") (name "Net-(M5-OB)") (class "Default")
      (node (ref "C6") (pin "2") (pinfunction "2_2") (pintype "passive"))
      (node (ref "J5") (pin "3") (pinfunction "3_3") (pintype "bidirectional"))
      (node (ref "M5") (pin "4") (pinfunction "OB_4") (pintype "bidirectional"))
      (node (ref "TP7") (pin "TP") (pinfunction "TP_TP") (pintype "input"))
    )
    (net (code "62") (name "Net-(M6-OA)") (class "Default")
      (node (ref "C9") (pin "1") (pinfunction "1_1") (pintype "passive"))
      (node (ref "J6") (pin "1") (pinfunction "1_1") (pintype "bidirectional"))
      (node (ref "M6") (pin "1") (pinfunction "OA_1") (pintype "bidirectional"))
      (node (ref "TP1") (pin "TP") (pinfunction "TP_TP") (pintype "input"))
    )
    (net (code "63") (name "Net-(M6-OB)") (class "Default")
      (node (ref "C9") (pin "2") (pinfunction "2_2") (pintype "passive"))
      (node (ref "J6") (pin "3") (pinfunction "3_3") (pintype "bidirectional"))
      (node (ref "M6") (pin "4") (pinfunction "OB_4") (pintype "bidirectional"))
      (node (ref "TP3") (pin "TP") (pinfunction "TP_TP") (pintype "input"))
    )
    (net (code "64") (name "VCC") (class "Default")
      (node (ref "1WIRE") (pin "3") (pinfunction "3_3") (pintype "passive"))
      (node (ref "C10") (pin "2") (pinfunction "2_2") (pintype "passive"))
      (node (ref "C11") (pin "1") (pinfunction "1_1") (pintype "passive"))
      (node (ref "C12") (pin "2") (pinfunction "2_2") (pintype "passive"))
      (node (ref "C13") (pin "2") (pinfunction "2_2") (pintype "passive"))
      (node (ref "C14") (pin "2") (pinfunction "2_2") (pintype "passive"))
      (node (ref "C15") (pin "2") (pinfunction "2_2") (pintype "passive"))
      (node (ref "C16") (pin "2") (pinfunction "2_2") (pintype "passive"))
      (node (ref "C19") (pin "+") (pinfunction "+_+") (pintype "passive"))
      (node (ref "C2") (pin "2") (pinfunction "2_2") (pintype "passive"))
      (node (ref "C7") (pin "1") (pinfunction "1_1") (pintype "passive"))
      (node (ref "IC1") (pin "4") (pinfunction "VCC_4") (pintype "power_in"))
      (node (ref "IC1") (pin "6") (pinfunction "VCC_6") (pintype "power_in"))
      (node (ref "IC2") (pin "4") (pinfunction "OUT_4") (pintype "passive"))
      (node (ref "JP3") (pin "1") (pinfunction "1_1") (pintype "passive"))
      (node (ref "L1") (pin "1") (pinfunction "1_1") (pintype "passive"))
      (node (ref "LED2") (pin "A") (pinfunction "A_A") (pintype "passive"))
      (node (ref "M1") (pin "2") (pinfunction "VCC_2") (pintype "bidirectional"))
      (node (ref "M1") (pin "3") (pinfunction "VCC_3") (pintype "bidirectional"))
      (node (ref "M2") (pin "2") (pinfunction "VCC_2") (pintype "bidirectional"))
      (node (ref "M2") (pin "3") (pinfunction "VCC_3") (pintype "bidirectional"))
      (node (ref "M3") (pin "2") (pinfunction "VCC_2") (pintype "bidirectional"))
      (node (ref "M3") (pin "3") (pinfunction "VCC_3") (pintype "bidirectional"))
      (node (ref "M4") (pin "2") (pinfunction "VCC_2") (pintype "bidirectional"))
      (node (ref "M4") (pin "3") (pinfunction "VCC_3") (pintype "bidirectional"))
      (node (ref "M5") (pin "2") (pinfunction "VCC_2") (pintype "bidirectional"))
      (node (ref "M5") (pin "3") (pinfunction "VCC_3") (pintype "bidirectional"))
      (node (ref "M6") (pin "2") (pinfunction "VCC_2") (pintype "bidirectional"))
      (node (ref "M6") (pin "3") (pinfunction "VCC_3") (pintype "bidirectional"))
      (node (ref "R11") (pin "1") (pinfunction "1_1") (pintype "passive"))
      (node (ref "R12") (pin "1") (pinfunction "1_1") (pintype "passive"))
      (node (ref "R14") (pin "1") (pinfunction "1_1") (pintype "passive"))
      (node (ref "R15") (pin "1") (pinfunction "1_1") (pintype "passive"))
      (node (ref "R16") (pin "1") (pinfunction "1_1") (pintype "passive"))
      (node (ref "R18") (pin "1") (pinfunction "1_1") (pintype "passive"))
      (node (ref "R19") (pin "1") (pinfunction "1_1") (pintype "passive"))
      (node (ref "R2") (pin "1") (pinfunction "1_1") (pintype "passive"))
      (node (ref "R20") (pin "1") (pinfunction "1_1") (pintype "passive"))
      (node (ref "R21") (pin "1") (pinfunction "1_1") (pintype "passive"))
      (node (ref "R22") (pin "1") (pinfunction "1_1") (pintype "passive"))
      (node (ref "R23") (pin "1") (pinfunction "1_1") (pintype "passive"))
      (node (ref "R25") (pin "1") (pinfunction "1_1") (pintype "passive"))
      (node (ref "R27") (pin "2") (pinfunction "2_2") (pintype "passive"))
      (node (ref "R3") (pin "1") (pinfunction "1_1") (pintype "passive"))
      (node (ref "R5") (pin "1") (pinfunction "1_1") (pintype "passive"))
      (node (ref "R6") (pin "1") (pinfunction "1_1") (pintype "passive"))
      (node (ref "R8") (pin "1") (pinfunction "1_1") (pintype "passive"))
      (node (ref "R9") (pin "1") (pinfunction "1_1") (pintype "passive"))
      (node (ref "U$1") (pin "CH_PD") (pinfunction "CH_PD_CH_PD") (pintype "bidirectional"))
      (node (ref "U$1") (pin "VCC") (pinfunction "VCC_VCC") (pintype "bidirectional"))
    )
    (net (code "65") (name "unconnected-(U$1-PadADC)") (class "Default")
      (node (ref "U$1") (pin "ADC") (pinfunction "ADC_ADC") (pintype "bidirectional"))
    )
    (net (code "66") (name "unconnected-(U$1-PadGPIO12)") (class "Default")
      (node (ref "U$1") (pin "GPIO12") (pinfunction "GPIO12_GPIO12") (pintype "bidirectional"))
    )
    (net (code "67") (name "unconnected-(U$1-PadGPIO13)") (class "Default")
      (node (ref "U$1") (pin "GPIO13") (pinfunction "GPIO13_GPIO13") (pintype "bidirectional"))
    )
    (net (code "68") (name "unconnected-(U$1-PadGPIO14)") (class "Default")
      (node (ref "U$1") (pin "GPIO14") (pinfunction "GPIO14_GPIO14") (pintype "bidirectional"))
    )
    (net (code "69") (name "unconnected-(U$1-PadGPIO15)") (class "Default")
      (node (ref "U$1") (pin "GPIO15") (pinfunction "GPIO15_GPIO15") (pintype "bidirectional"))
    )
  )
)
